# SCH_CardPCB_2025-11-23.net
KiCad netlist of a schematic drawn in EasyEDA
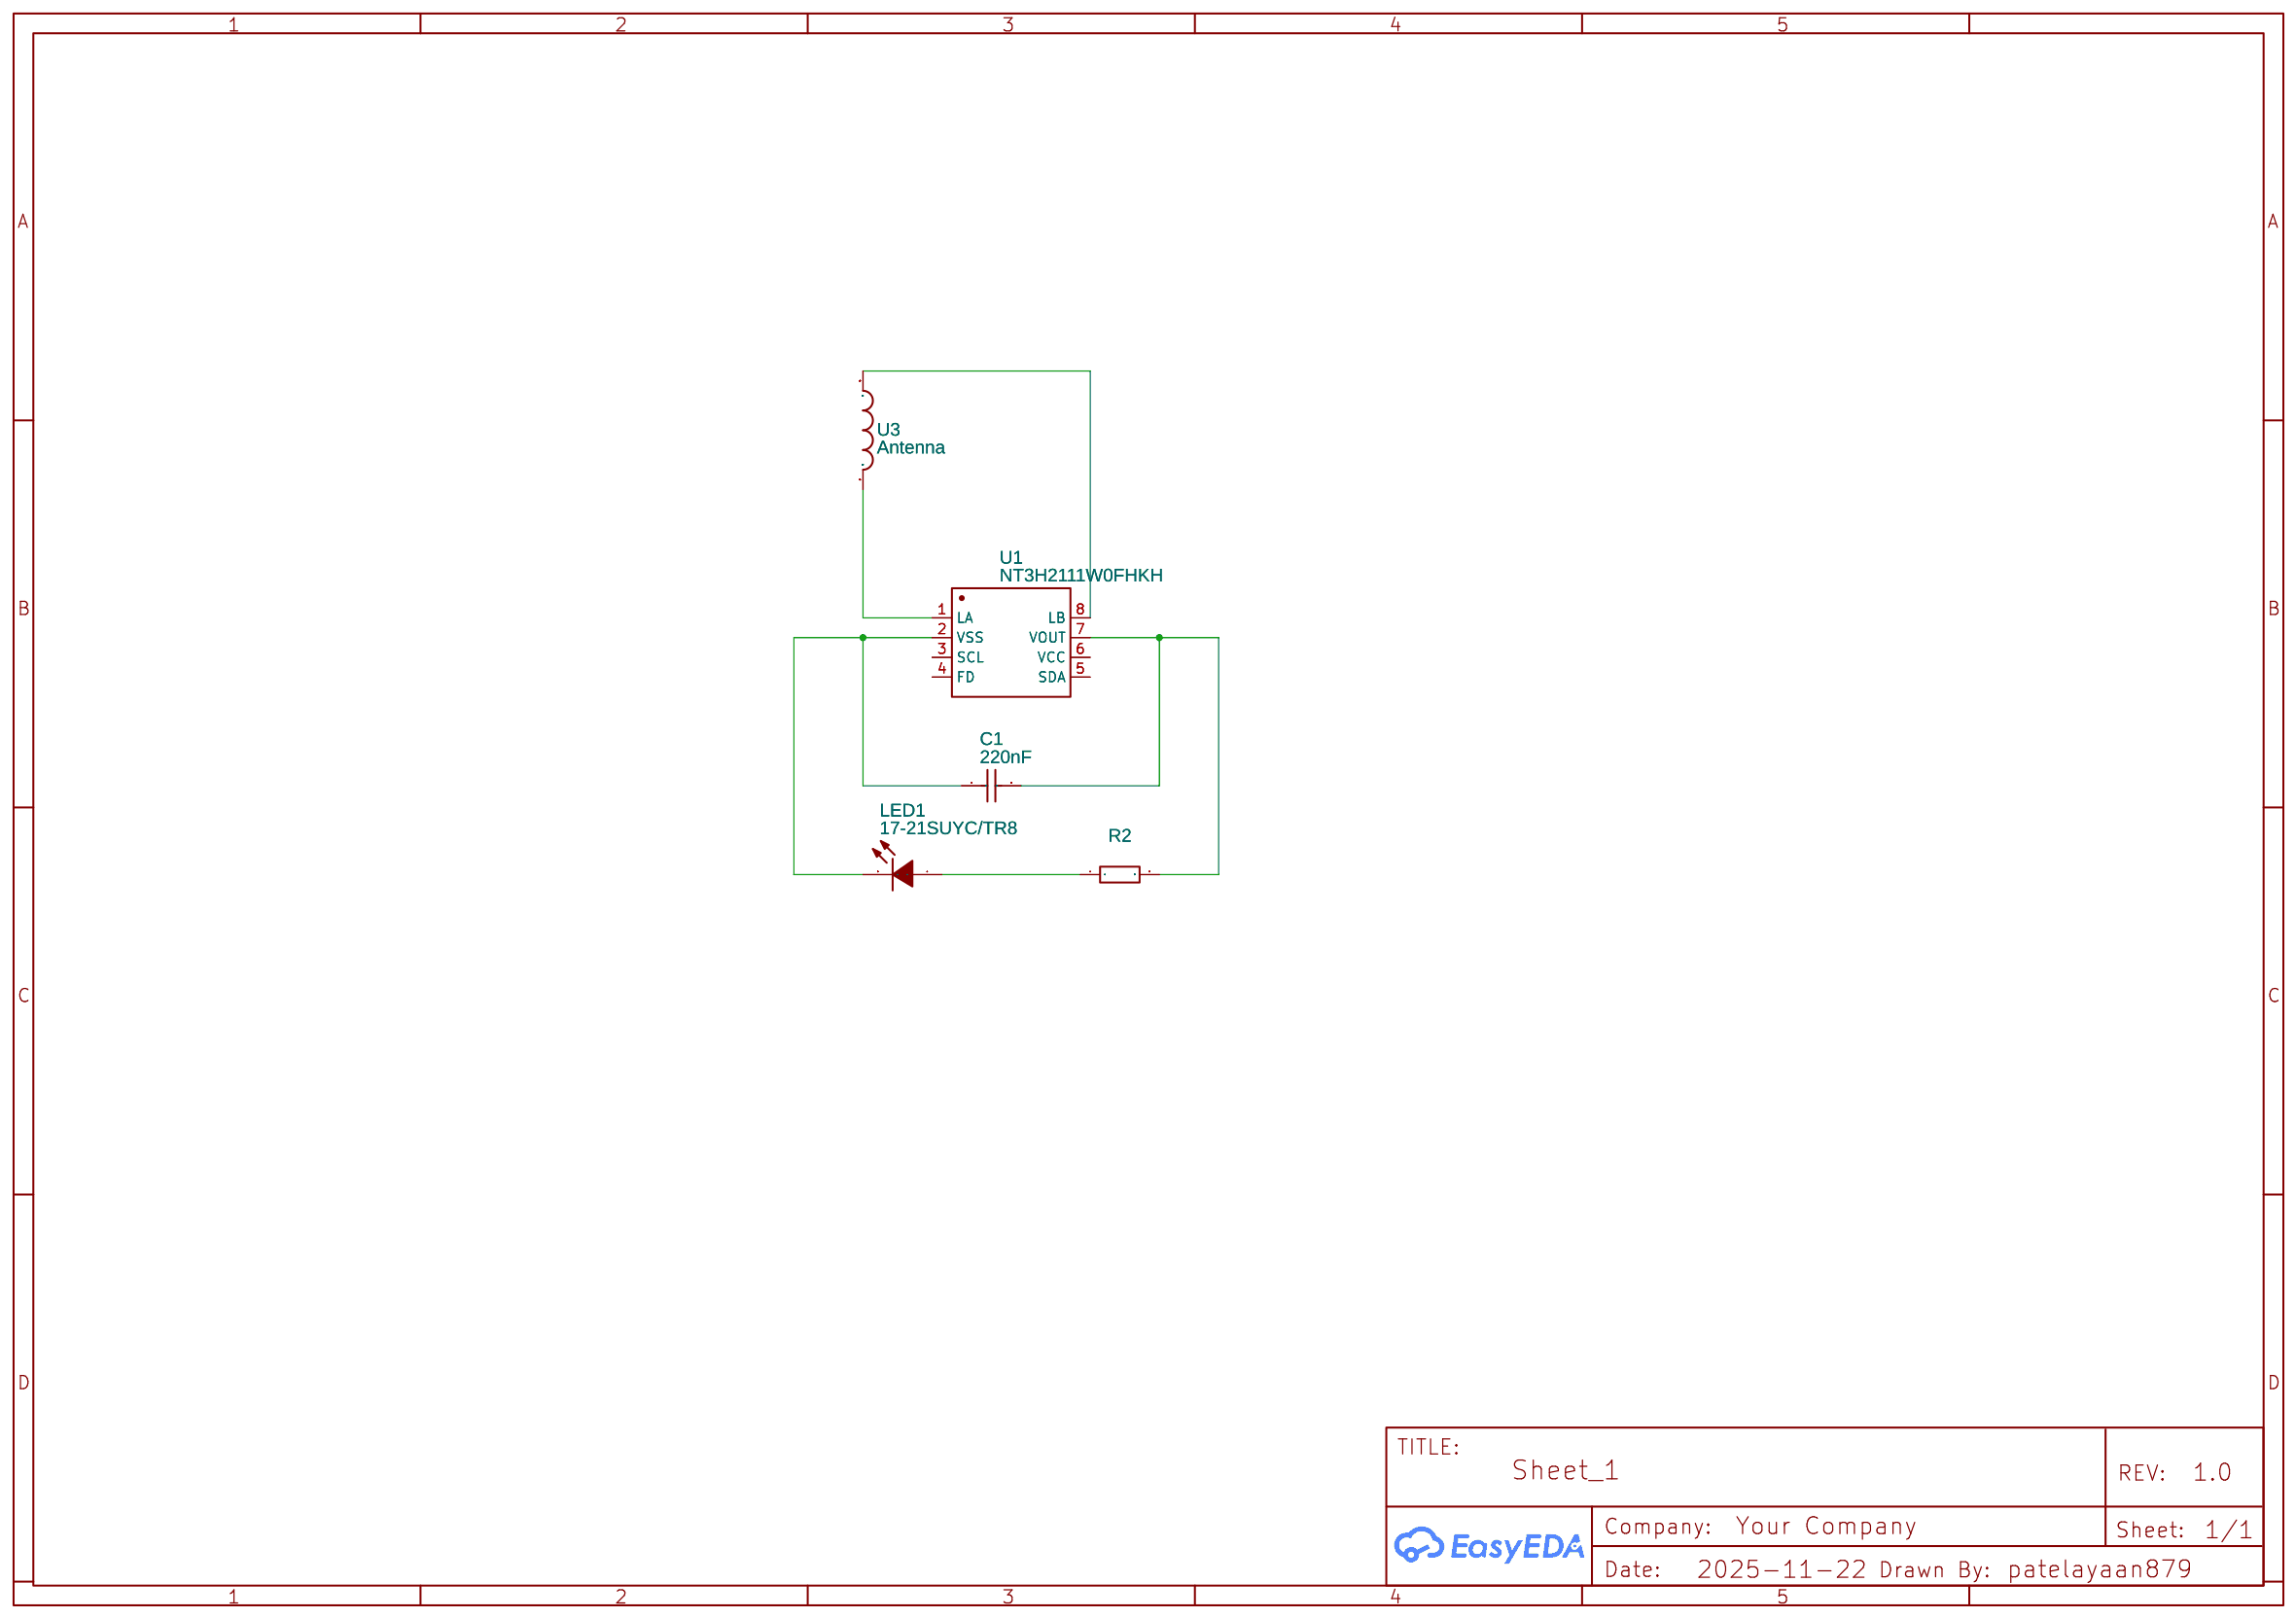
[diagram p0: schematic sheet]

(export (version "E")
  (design (tool "Eeschema 10.0.6"))
  (components
    (comp (ref "C1")
      (value "220nF")
      (fields
        (field (name "Manufacturer Part") "CL10B224KA8NNNC")
        (field (name "Manufacturer") "SAMSUNG(三星)")
      )
      (libsource (lib "") (part "CL10B224KA8NNNC"))
    )
    (comp (ref "LED1")
      (value "17-21SUYC/TR8")
      (fields (field (name "Manufacturer Part") "KT-0805黄灯") (field (name "Manufacturer") "KENTO"))
      (libsource (lib "") (part "17-21SUYC/TR8"))
    )
    (comp (ref "R2")
      (value "47Ω")
      (fields
        (field (name "Manufacturer Part") "0603WAF470JT5E")
        (field (name "Manufacturer") "UNI-ROYAL(厚声)")
      )
      (libsource (lib "") (part "0603WAF470JT5E"))
    )
    (comp (ref "U1")
      (value "NT3H2111W0FHKH")
      (fields (field (name "Manufacturer") "NXP(恩智浦)"))
      (libsource (lib "") (part "NT3H2111W0FHKH"))
    )
    (comp (ref "U3") (value "Antenna") (libsource (lib "") (part "Antenna")))
  )
  (nets
    (net (code "1") (name "Net-(LED1-+)") (class "Default")
      (node (ref "LED1") (pin "1") (pinfunction "+_1") (pintype "unspecified"))
      (node (ref "R2") (pin "1") (pinfunction "1_1") (pintype "input"))
    )
    (net (code "2") (name "Net-(LED1--)") (class "Default")
      (node (ref "C1") (pin "1") (pinfunction "1_1") (pintype "input"))
      (node (ref "LED1") (pin "2") (pinfunction "-_2") (pintype "unspecified"))
      (node (ref "U1") (pin "2") (pinfunction "VSS_2") (pintype "unspecified"))
    )
    (net (code "3") (name "Net-(U1-LA)") (class "Default")
      (node (ref "U1") (pin "1") (pinfunction "LA_1") (pintype "unspecified"))
      (node (ref "U3") (pin "P$1") (pinfunction "P$1_P$1") (pintype "unspecified"))
    )
    (net (code "4") (name "Net-(U1-LB)") (class "Default")
      (node (ref "U1") (pin "8") (pinfunction "LB_8") (pintype "unspecified"))
      (node (ref "U3") (pin "P$2") (pinfunction "P$2_P$2") (pintype "unspecified"))
    )
    (net (code "5") (name "Net-(U1-VOUT)") (class "Default")
      (node (ref "C1") (pin "2") (pinfunction "2_2") (pintype "input"))
      (node (ref "R2") (pin "2") (pinfunction "2_2") (pintype "input"))
      (node (ref "U1") (pin "7") (pinfunction "VOUT_7") (pintype "unspecified"))
    )
    (net (code "6") (name "unconnected-(U1-FD-Pad4)") (class "Default")
      (node (ref "U1") (pin "4") (pinfunction "FD_4") (pintype "unspecified"))
    )
    (net (code "7") (name "unconnected-(U1-SCL-Pad3)") (class "Default")
      (node (ref "U1") (pin "3") (pinfunction "SCL_3") (pintype "unspecified"))
    )
    (net (code "8") (name "unconnected-(U1-SDA-Pad5)") (class "Default")
      (node (ref "U1") (pin "5") (pinfunction "SDA_5") (pintype "unspecified"))
    )
    (net (code "9") (name "unconnected-(U1-VCC-Pad6)") (class "Default")
      (node (ref "U1") (pin "6") (pinfunction "VCC_6") (pintype "unspecified"))
    )
  )
)
